# flatsat.net
KiCad netlist of a schematic drawn in EAGLE
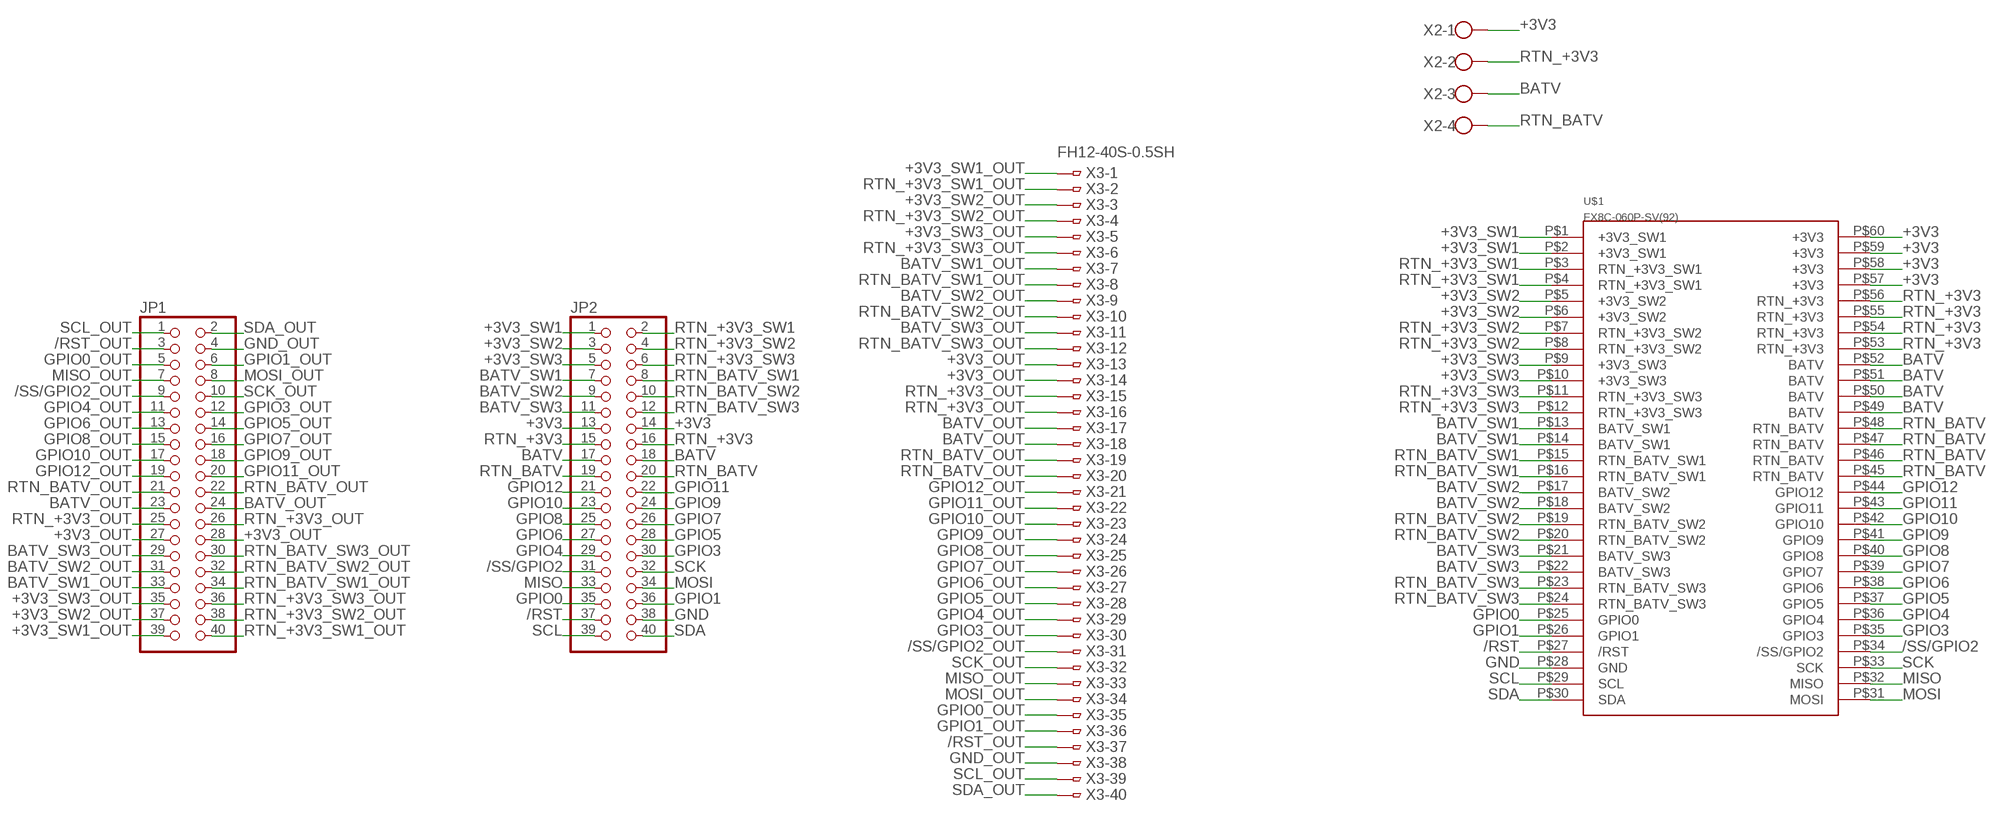
[diagram p0: schematic, sheet 1]

(export (version "E")
  (design (tool "Eeschema 10.0.6"))
  (components
    (comp (ref "JP1")
      (value "PINHD-2X20/90")
      (footprint "eagle-import:2X20_90")
      (libsource (lib "eagle-import") (part "PINHD-2X20/90"))
    )
    (comp (ref "JP2")
      (value "PINHD-2X20/90")
      (footprint "eagle-import:2X20_90")
      (libsource (lib "eagle-import") (part "PINHD-2X20/90"))
    )
    (comp (ref "U$1")
      (value "FX8C-060P-SV(92)")
      (footprint "eagle-import:FX8C-060P-SV(92)")
      (libsource (lib "eagle-import") (part "FX8C-060P-SV(92)"))
    )
    (comp (ref "X2")
      (value "W237-4")
      (footprint "eagle-import:W237-4")
      (libsource (lib "eagle-import") (part "W237-4"))
    )
    (comp (ref "X3")
      (value "FH12-40S-0.5SH")
      (footprint "eagle-import:FH12-40S-0.5SH")
      (fields (field (name "MPN") "FH12-40S-0.5SH(55)"))
      (libsource (lib "eagle-import") (part "FH12-40S-0.5SH"))
    )
  )
  (nets
    (net (code "1") (name "/+3V3") (class "Default")
      (node (ref "JP2") (pin "13") (pinfunction "13_13") (pintype "passive"))
      (node (ref "JP2") (pin "14") (pinfunction "14_14") (pintype "passive"))
      (node (ref "U$1") (pin "P$57") (pinfunction "+3V3_P$57") (pintype "power_in"))
      (node (ref "U$1") (pin "P$58") (pinfunction "+3V3_P$58") (pintype "power_in"))
      (node (ref "U$1") (pin "P$59") (pinfunction "+3V3_P$59") (pintype "power_in"))
      (node (ref "U$1") (pin "P$60") (pinfunction "+3V3_P$60") (pintype "power_in"))
      (node (ref "X2") (pin "1") (pinfunction "KL_1") (pintype "passive"))
    )
    (net (code "2") (name "/+3V3_OUT") (class "Default")
      (node (ref "JP1") (pin "27") (pinfunction "27_27") (pintype "passive"))
      (node (ref "JP1") (pin "28") (pinfunction "28_28") (pintype "passive"))
      (node (ref "X3") (pin "13") (pinfunction "1_13") (pintype "passive"))
      (node (ref "X3") (pin "14") (pinfunction "1_14") (pintype "passive"))
    )
    (net (code "3") (name "/+3V3_SW1") (class "Default")
      (node (ref "JP2") (pin "1") (pinfunction "1_1") (pintype "passive"))
      (node (ref "U$1") (pin "P$1") (pinfunction "+3V3_SW1_P$1") (pintype "power_in"))
      (node (ref "U$1") (pin "P$2") (pinfunction "+3V3_SW1_P$2") (pintype "power_in"))
    )
    (net (code "4") (name "/+3V3_SW1_OUT") (class "Default")
      (node (ref "JP1") (pin "39") (pinfunction "39_39") (pintype "passive"))
      (node (ref "X3") (pin "1") (pinfunction "1_1") (pintype "passive"))
    )
    (net (code "5") (name "/+3V3_SW2") (class "Default")
      (node (ref "JP2") (pin "3") (pinfunction "3_3") (pintype "passive"))
      (node (ref "U$1") (pin "P$5") (pinfunction "+3V3_SW2_P$5") (pintype "power_in"))
      (node (ref "U$1") (pin "P$6") (pinfunction "+3V3_SW2_P$6") (pintype "power_in"))
    )
    (net (code "6") (name "/+3V3_SW2_OUT") (class "Default")
      (node (ref "JP1") (pin "37") (pinfunction "37_37") (pintype "passive"))
      (node (ref "X3") (pin "3") (pinfunction "1_3") (pintype "passive"))
    )
    (net (code "7") (name "/+3V3_SW3") (class "Default")
      (node (ref "JP2") (pin "5") (pinfunction "5_5") (pintype "passive"))
      (node (ref "U$1") (pin "P$10") (pinfunction "+3V3_SW3_P$10") (pintype "power_in"))
      (node (ref "U$1") (pin "P$9") (pinfunction "+3V3_SW3_P$9") (pintype "power_in"))
    )
    (net (code "8") (name "/+3V3_SW3_OUT") (class "Default")
      (node (ref "JP1") (pin "35") (pinfunction "35_35") (pintype "passive"))
      (node (ref "X3") (pin "5") (pinfunction "1_5") (pintype "passive"))
    )
    (net (code "9") (name "/BATV") (class "Default")
      (node (ref "JP2") (pin "17") (pinfunction "17_17") (pintype "passive"))
      (node (ref "JP2") (pin "18") (pinfunction "18_18") (pintype "passive"))
      (node (ref "U$1") (pin "P$49") (pinfunction "BATV_P$49") (pintype "power_in"))
      (node (ref "U$1") (pin "P$50") (pinfunction "BATV_P$50") (pintype "power_in"))
      (node (ref "U$1") (pin "P$51") (pinfunction "BATV_P$51") (pintype "power_in"))
      (node (ref "U$1") (pin "P$52") (pinfunction "BATV_P$52") (pintype "power_in"))
      (node (ref "X2") (pin "3") (pinfunction "KL_3") (pintype "passive"))
    )
    (net (code "10") (name "/BATV_OUT") (class "Default")
      (node (ref "JP1") (pin "23") (pinfunction "23_23") (pintype "passive"))
      (node (ref "JP1") (pin "24") (pinfunction "24_24") (pintype "passive"))
      (node (ref "X3") (pin "17") (pinfunction "1_17") (pintype "passive"))
      (node (ref "X3") (pin "18") (pinfunction "1_18") (pintype "passive"))
    )
    (net (code "11") (name "/BATV_SW1") (class "Default")
      (node (ref "JP2") (pin "7") (pinfunction "7_7") (pintype "passive"))
      (node (ref "U$1") (pin "P$13") (pinfunction "BATV_SW1_P$13") (pintype "power_in"))
      (node (ref "U$1") (pin "P$14") (pinfunction "BATV_SW1_P$14") (pintype "power_in"))
    )
    (net (code "12") (name "/BATV_SW1_OUT") (class "Default")
      (node (ref "JP1") (pin "33") (pinfunction "33_33") (pintype "passive"))
      (node (ref "X3") (pin "7") (pinfunction "1_7") (pintype "passive"))
    )
    (net (code "13") (name "/BATV_SW2") (class "Default")
      (node (ref "JP2") (pin "9") (pinfunction "9_9") (pintype "passive"))
      (node (ref "U$1") (pin "P$17") (pinfunction "BATV_SW2_P$17") (pintype "power_in"))
      (node (ref "U$1") (pin "P$18") (pinfunction "BATV_SW2_P$18") (pintype "power_in"))
    )
    (net (code "14") (name "/BATV_SW2_OUT") (class "Default")
      (node (ref "JP1") (pin "31") (pinfunction "31_31") (pintype "passive"))
      (node (ref "X3") (pin "9") (pinfunction "1_9") (pintype "passive"))
    )
    (net (code "15") (name "/BATV_SW3") (class "Default")
      (node (ref "JP2") (pin "11") (pinfunction "11_11") (pintype "passive"))
      (node (ref "U$1") (pin "P$21") (pinfunction "BATV_SW3_P$21") (pintype "power_in"))
      (node (ref "U$1") (pin "P$22") (pinfunction "BATV_SW3_P$22") (pintype "power_in"))
    )
    (net (code "16") (name "/BATV_SW3_OUT") (class "Default")
      (node (ref "JP1") (pin "29") (pinfunction "29_29") (pintype "passive"))
      (node (ref "X3") (pin "11") (pinfunction "1_11") (pintype "passive"))
    )
    (net (code "17") (name "/GND") (class "Default")
      (node (ref "JP2") (pin "38") (pinfunction "38_38") (pintype "passive"))
      (node (ref "U$1") (pin "P$28") (pinfunction "GND_P$28") (pintype "bidirectional"))
    )
    (net (code "18") (name "/GND_OUT") (class "Default")
      (node (ref "JP1") (pin "4") (pinfunction "4_4") (pintype "passive"))
      (node (ref "X3") (pin "38") (pinfunction "1_38") (pintype "passive"))
    )
    (net (code "19") (name "/GPIO0") (class "Default")
      (node (ref "JP2") (pin "35") (pinfunction "35_35") (pintype "passive"))
      (node (ref "U$1") (pin "P$25") (pinfunction "GPIO0_P$25") (pintype "bidirectional"))
    )
    (net (code "20") (name "/GPIO0_OUT") (class "Default")
      (node (ref "JP1") (pin "5") (pinfunction "5_5") (pintype "passive"))
      (node (ref "X3") (pin "35") (pinfunction "1_35") (pintype "passive"))
    )
    (net (code "21") (name "/GPIO1") (class "Default")
      (node (ref "JP2") (pin "36") (pinfunction "36_36") (pintype "passive"))
      (node (ref "U$1") (pin "P$26") (pinfunction "GPIO1_P$26") (pintype "bidirectional"))
    )
    (net (code "22") (name "/GPIO1_OUT") (class "Default")
      (node (ref "JP1") (pin "6") (pinfunction "6_6") (pintype "passive"))
      (node (ref "X3") (pin "36") (pinfunction "1_36") (pintype "passive"))
    )
    (net (code "23") (name "/GPIO3") (class "Default")
      (node (ref "JP2") (pin "30") (pinfunction "30_30") (pintype "passive"))
      (node (ref "U$1") (pin "P$35") (pinfunction "GPIO3_P$35") (pintype "bidirectional"))
    )
    (net (code "24") (name "/GPIO3_OUT") (class "Default")
      (node (ref "JP1") (pin "12") (pinfunction "12_12") (pintype "passive"))
      (node (ref "X3") (pin "30") (pinfunction "1_30") (pintype "passive"))
    )
    (net (code "25") (name "/GPIO4") (class "Default")
      (node (ref "JP2") (pin "29") (pinfunction "29_29") (pintype "passive"))
      (node (ref "U$1") (pin "P$36") (pinfunction "GPIO4_P$36") (pintype "bidirectional"))
    )
    (net (code "26") (name "/GPIO4_OUT") (class "Default")
      (node (ref "JP1") (pin "11") (pinfunction "11_11") (pintype "passive"))
      (node (ref "X3") (pin "29") (pinfunction "1_29") (pintype "passive"))
    )
    (net (code "27") (name "/GPIO5") (class "Default")
      (node (ref "JP2") (pin "28") (pinfunction "28_28") (pintype "passive"))
      (node (ref "U$1") (pin "P$37") (pinfunction "GPIO5_P$37") (pintype "bidirectional"))
    )
    (net (code "28") (name "/GPIO5_OUT") (class "Default")
      (node (ref "JP1") (pin "14") (pinfunction "14_14") (pintype "passive"))
      (node (ref "X3") (pin "28") (pinfunction "1_28") (pintype "passive"))
    )
    (net (code "29") (name "/GPIO6") (class "Default")
      (node (ref "JP2") (pin "27") (pinfunction "27_27") (pintype "passive"))
      (node (ref "U$1") (pin "P$38") (pinfunction "GPIO6_P$38") (pintype "bidirectional"))
    )
    (net (code "30") (name "/GPIO6_OUT") (class "Default")
      (node (ref "JP1") (pin "13") (pinfunction "13_13") (pintype "passive"))
      (node (ref "X3") (pin "27") (pinfunction "1_27") (pintype "passive"))
    )
    (net (code "31") (name "/GPIO7") (class "Default")
      (node (ref "JP2") (pin "26") (pinfunction "26_26") (pintype "passive"))
      (node (ref "U$1") (pin "P$39") (pinfunction "GPIO7_P$39") (pintype "bidirectional"))
    )
    (net (code "32") (name "/GPIO7_OUT") (class "Default")
      (node (ref "JP1") (pin "16") (pinfunction "16_16") (pintype "passive"))
      (node (ref "X3") (pin "26") (pinfunction "1_26") (pintype "passive"))
    )
    (net (code "33") (name "/GPIO8") (class "Default")
      (node (ref "JP2") (pin "25") (pinfunction "25_25") (pintype "passive"))
      (node (ref "U$1") (pin "P$40") (pinfunction "GPIO8_P$40") (pintype "bidirectional"))
    )
    (net (code "34") (name "/GPIO8_OUT") (class "Default")
      (node (ref "JP1") (pin "15") (pinfunction "15_15") (pintype "passive"))
      (node (ref "X3") (pin "25") (pinfunction "1_25") (pintype "passive"))
    )
    (net (code "35") (name "/GPIO9") (class "Default")
      (node (ref "JP2") (pin "24") (pinfunction "24_24") (pintype "passive"))
      (node (ref "U$1") (pin "P$41") (pinfunction "GPIO9_P$41") (pintype "bidirectional"))
    )
    (net (code "36") (name "/GPIO9_OUT") (class "Default")
      (node (ref "JP1") (pin "18") (pinfunction "18_18") (pintype "passive"))
      (node (ref "X3") (pin "24") (pinfunction "1_24") (pintype "passive"))
    )
    (net (code "37") (name "/GPIO10") (class "Default")
      (node (ref "JP2") (pin "23") (pinfunction "23_23") (pintype "passive"))
      (node (ref "U$1") (pin "P$42") (pinfunction "GPIO10_P$42") (pintype "bidirectional"))
    )
    (net (code "38") (name "/GPIO10_OUT") (class "Default")
      (node (ref "JP1") (pin "17") (pinfunction "17_17") (pintype "passive"))
      (node (ref "X3") (pin "23") (pinfunction "1_23") (pintype "passive"))
    )
    (net (code "39") (name "/GPIO11") (class "Default")
      (node (ref "JP2") (pin "22") (pinfunction "22_22") (pintype "passive"))
      (node (ref "U$1") (pin "P$43") (pinfunction "GPIO11_P$43") (pintype "bidirectional"))
    )
    (net (code "40") (name "/GPIO11_OUT") (class "Default")
      (node (ref "JP1") (pin "20") (pinfunction "20_20") (pintype "passive"))
      (node (ref "X3") (pin "22") (pinfunction "1_22") (pintype "passive"))
    )
    (net (code "41") (name "/GPIO12") (class "Default")
      (node (ref "JP2") (pin "21") (pinfunction "21_21") (pintype "passive"))
      (node (ref "U$1") (pin "P$44") (pinfunction "GPIO12_P$44") (pintype "bidirectional"))
    )
    (net (code "42") (name "/GPIO12_OUT") (class "Default")
      (node (ref "JP1") (pin "19") (pinfunction "19_19") (pintype "passive"))
      (node (ref "X3") (pin "21") (pinfunction "1_21") (pintype "passive"))
    )
    (net (code "43") (name "/MISO") (class "Default")
      (node (ref "JP2") (pin "33") (pinfunction "33_33") (pintype "passive"))
      (node (ref "U$1") (pin "P$32") (pinfunction "MISO_P$32") (pintype "bidirectional"))
    )
    (net (code "44") (name "/MISO_OUT") (class "Default")
      (node (ref "JP1") (pin "7") (pinfunction "7_7") (pintype "passive"))
      (node (ref "X3") (pin "33") (pinfunction "1_33") (pintype "passive"))
    )
    (net (code "45") (name "/MOSI") (class "Default")
      (node (ref "JP2") (pin "34") (pinfunction "34_34") (pintype "passive"))
      (node (ref "U$1") (pin "P$31") (pinfunction "MOSI_P$31") (pintype "bidirectional"))
    )
    (net (code "46") (name "/MOSI_OUT") (class "Default")
      (node (ref "JP1") (pin "8") (pinfunction "8_8") (pintype "passive"))
      (node (ref "X3") (pin "34") (pinfunction "1_34") (pintype "passive"))
    )
    (net (code "47") (name "/RTN_+3V3") (class "Default")
      (node (ref "JP2") (pin "15") (pinfunction "15_15") (pintype "passive"))
      (node (ref "JP2") (pin "16") (pinfunction "16_16") (pintype "passive"))
      (node (ref "U$1") (pin "P$53") (pinfunction "RTN_+3V3_P$53") (pintype "power_in"))
      (node (ref "U$1") (pin "P$54") (pinfunction "RTN_+3V3_P$54") (pintype "power_in"))
      (node (ref "U$1") (pin "P$55") (pinfunction "RTN_+3V3_P$55") (pintype "power_in"))
      (node (ref "U$1") (pin "P$56") (pinfunction "RTN_+3V3_P$56") (pintype "power_in"))
      (node (ref "X2") (pin "2") (pinfunction "KL_2") (pintype "passive"))
    )
    (net (code "48") (name "/RTN_+3V3_OUT") (class "Default")
      (node (ref "JP1") (pin "25") (pinfunction "25_25") (pintype "passive"))
      (node (ref "JP1") (pin "26") (pinfunction "26_26") (pintype "passive"))
      (node (ref "X3") (pin "15") (pinfunction "1_15") (pintype "passive"))
      (node (ref "X3") (pin "16") (pinfunction "1_16") (pintype "passive"))
    )
    (net (code "49") (name "/RTN_+3V3_SW1") (class "Default")
      (node (ref "JP2") (pin "2") (pinfunction "2_2") (pintype "passive"))
      (node (ref "U$1") (pin "P$3") (pinfunction "RTN_+3V3_SW1_P$3") (pintype "power_in"))
      (node (ref "U$1") (pin "P$4") (pinfunction "RTN_+3V3_SW1_P$4") (pintype "power_in"))
    )
    (net (code "50") (name "/RTN_+3V3_SW1_OUT") (class "Default")
      (node (ref "JP1") (pin "40") (pinfunction "40_40") (pintype "passive"))
      (node (ref "X3") (pin "2") (pinfunction "1_2") (pintype "passive"))
    )
    (net (code "51") (name "/RTN_+3V3_SW2") (class "Default")
      (node (ref "JP2") (pin "4") (pinfunction "4_4") (pintype "passive"))
      (node (ref "U$1") (pin "P$7") (pinfunction "RTN_+3V3_SW2_P$7") (pintype "power_in"))
      (node (ref "U$1") (pin "P$8") (pinfunction "RTN_+3V3_SW2_P$8") (pintype "power_in"))
    )
    (net (code "52") (name "/RTN_+3V3_SW2_OUT") (class "Default")
      (node (ref "JP1") (pin "38") (pinfunction "38_38") (pintype "passive"))
      (node (ref "X3") (pin "4") (pinfunction "1_4") (pintype "passive"))
    )
    (net (code "53") (name "/RTN_+3V3_SW3") (class "Default")
      (node (ref "JP2") (pin "6") (pinfunction "6_6") (pintype "passive"))
      (node (ref "U$1") (pin "P$11") (pinfunction "RTN_+3V3_SW3_P$11") (pintype "power_in"))
      (node (ref "U$1") (pin "P$12") (pinfunction "RTN_+3V3_SW3_P$12") (pintype "power_in"))
    )
    (net (code "54") (name "/RTN_+3V3_SW3_OUT") (class "Default")
      (node (ref "JP1") (pin "36") (pinfunction "36_36") (pintype "passive"))
      (node (ref "X3") (pin "6") (pinfunction "1_6") (pintype "passive"))
    )
    (net (code "55") (name "/RTN_BATV") (class "Default")
      (node (ref "JP2") (pin "19") (pinfunction "19_19") (pintype "passive"))
      (node (ref "JP2") (pin "20") (pinfunction "20_20") (pintype "passive"))
      (node (ref "U$1") (pin "P$45") (pinfunction "RTN_BATV_P$45") (pintype "power_in"))
      (node (ref "U$1") (pin "P$46") (pinfunction "RTN_BATV_P$46") (pintype "power_in"))
      (node (ref "U$1") (pin "P$47") (pinfunction "RTN_BATV_P$47") (pintype "power_in"))
      (node (ref "U$1") (pin "P$48") (pinfunction "RTN_BATV_P$48") (pintype "power_in"))
      (node (ref "X2") (pin "4") (pinfunction "KL_4") (pintype "passive"))
    )
    (net (code "56") (name "/RTN_BATV_OUT") (class "Default")
      (node (ref "JP1") (pin "21") (pinfunction "21_21") (pintype "passive"))
      (node (ref "JP1") (pin "22") (pinfunction "22_22") (pintype "passive"))
      (node (ref "X3") (pin "19") (pinfunction "1_19") (pintype "passive"))
      (node (ref "X3") (pin "20") (pinfunction "1_20") (pintype "passive"))
    )
    (net (code "57") (name "/RTN_BATV_SW1") (class "Default")
      (node (ref "JP2") (pin "8") (pinfunction "8_8") (pintype "passive"))
      (node (ref "U$1") (pin "P$15") (pinfunction "RTN_BATV_SW1_P$15") (pintype "power_in"))
      (node (ref "U$1") (pin "P$16") (pinfunction "RTN_BATV_SW1_P$16") (pintype "power_in"))
    )
    (net (code "58") (name "/RTN_BATV_SW1_OUT") (class "Default")
      (node (ref "JP1") (pin "34") (pinfunction "34_34") (pintype "passive"))
      (node (ref "X3") (pin "8") (pinfunction "1_8") (pintype "passive"))
    )
    (net (code "59") (name "/RTN_BATV_SW2") (class "Default")
      (node (ref "JP2") (pin "10") (pinfunction "10_10") (pintype "passive"))
      (node (ref "U$1") (pin "P$19") (pinfunction "RTN_BATV_SW2_P$19") (pintype "power_in"))
      (node (ref "U$1") (pin "P$20") (pinfunction "RTN_BATV_SW2_P$20") (pintype "power_in"))
    )
    (net (code "60") (name "/RTN_BATV_SW2_OUT") (class "Default")
      (node (ref "JP1") (pin "32") (pinfunction "32_32") (pintype "passive"))
      (node (ref "X3") (pin "10") (pinfunction "1_10") (pintype "passive"))
    )
    (net (code "61") (name "/RTN_BATV_SW3") (class "Default")
      (node (ref "JP2") (pin "12") (pinfunction "12_12") (pintype "passive"))
      (node (ref "U$1") (pin "P$23") (pinfunction "RTN_BATV_SW3_P$23") (pintype "power_in"))
      (node (ref "U$1") (pin "P$24") (pinfunction "RTN_BATV_SW3_P$24") (pintype "power_in"))
    )
    (net (code "62") (name "/RTN_BATV_SW3_OUT") (class "Default")
      (node (ref "JP1") (pin "30") (pinfunction "30_30") (pintype "passive"))
      (node (ref "X3") (pin "12") (pinfunction "1_12") (pintype "passive"))
    )
    (net (code "63") (name "/SCK") (class "Default")
      (node (ref "JP2") (pin "32") (pinfunction "32_32") (pintype "passive"))
      (node (ref "U$1") (pin "P$33") (pinfunction "SCK_P$33") (pintype "bidirectional"))
    )
    (net (code "64") (name "/SCK_OUT") (class "Default")
      (node (ref "JP1") (pin "10") (pinfunction "10_10") (pintype "passive"))
      (node (ref "X3") (pin "32") (pinfunction "1_32") (pintype "passive"))
    )
    (net (code "65") (name "/SCL") (class "Default")
      (node (ref "JP2") (pin "39") (pinfunction "39_39") (pintype "passive"))
      (node (ref "U$1") (pin "P$29") (pinfunction "SCL_P$29") (pintype "bidirectional"))
    )
    (net (code "66") (name "/SCL_OUT") (class "Default")
      (node (ref "JP1") (pin "1") (pinfunction "1_1") (pintype "passive"))
      (node (ref "X3") (pin "39") (pinfunction "1_39") (pintype "passive"))
    )
    (net (code "67") (name "/SDA") (class "Default")
      (node (ref "JP2") (pin "40") (pinfunction "40_40") (pintype "passive"))
      (node (ref "U$1") (pin "P$30") (pinfunction "SDA_P$30") (pintype "bidirectional"))
    )
    (net (code "68") (name "/SDA_OUT") (class "Default")
      (node (ref "JP1") (pin "2") (pinfunction "2_2") (pintype "passive"))
      (node (ref "X3") (pin "40") (pinfunction "1_40") (pintype "passive"))
    )
    (net (code "69") (name "/{slash}RST") (class "Default")
      (node (ref "JP2") (pin "37") (pinfunction "37_37") (pintype "passive"))
      (node (ref "U$1") (pin "P$27") (pinfunction "/RST_P$27") (pintype "bidirectional"))
    )
    (net (code "70") (name "/{slash}RST_OUT") (class "Default")
      (node (ref "JP1") (pin "3") (pinfunction "3_3") (pintype "passive"))
      (node (ref "X3") (pin "37") (pinfunction "1_37") (pintype "passive"))
    )
    (net (code "71") (name "/{slash}SS{slash}GPIO2") (class "Default")
      (node (ref "JP2") (pin "31") (pinfunction "31_31") (pintype "passive"))
      (node (ref "U$1") (pin "P$34") (pinfunction "/SS/GPIO2_P$34") (pintype "bidirectional"))
    )
    (net (code "72") (name "/{slash}SS{slash}GPIO2_OUT") (class "Default")
      (node (ref "JP1") (pin "9") (pinfunction "9_9") (pintype "passive"))
      (node (ref "X3") (pin "31") (pinfunction "1_31") (pintype "passive"))
    )
  )
)
